# multiswitch2_2.net
KiCad netlist of a schematic drawn in EAGLE
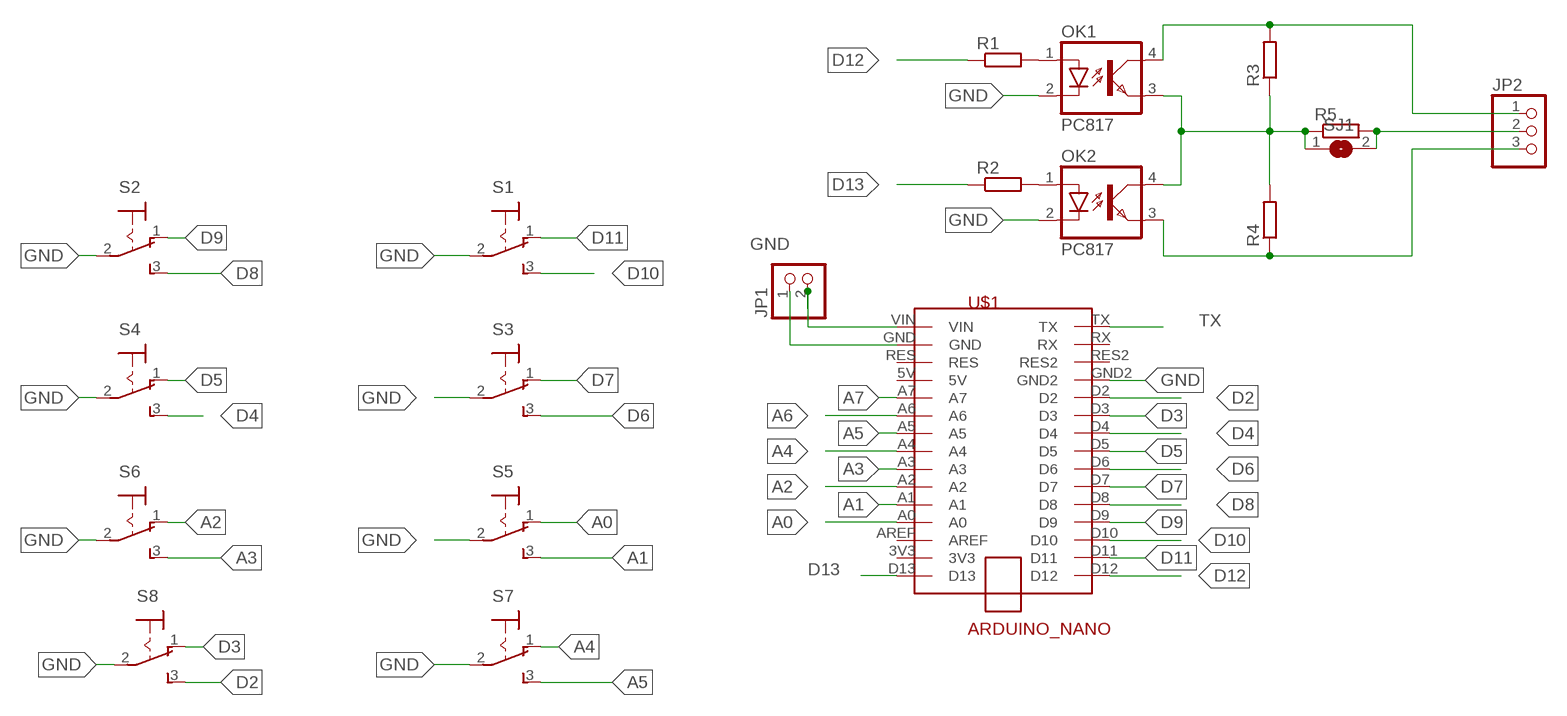
[diagram p0: schematic, sheet 1]

(export (version "E")
  (design (tool "Eeschema 10.0.6"))
  (components
    (comp (ref "JP1")
      (value "PINHD-1X2")
      (footprint "eagle-import:1X02")
      (libsource (lib "eagle-import") (part "PINHD-1X2"))
    )
    (comp (ref "JP2")
      (value "PINHD-1X3")
      (footprint "eagle-import:1X03")
      (libsource (lib "eagle-import") (part "PINHD-1X3"))
    )
    (comp (ref "OK1")
      (value "PC817")
      (footprint "eagle-import:DIL04")
      (fields (field (name "MPN") "PC817X4J000F"))
      (libsource (lib "eagle-import") (part "PC817"))
    )
    (comp (ref "OK2")
      (value "PC817")
      (footprint "eagle-import:DIL04")
      (fields (field (name "MPN") "PC817X4J000F"))
      (libsource (lib "eagle-import") (part "PC817"))
    )
    (comp (ref "R1")
      (value "R-EU_0204/7")
      (footprint "eagle-import:0204_7")
      (libsource (lib "eagle-import") (part "R-EU_0204/7"))
    )
    (comp (ref "R2")
      (value "R-EU_0204/7")
      (footprint "eagle-import:0204_7")
      (libsource (lib "eagle-import") (part "R-EU_0204/7"))
    )
    (comp (ref "R3")
      (value "R-EU_0204/7")
      (footprint "eagle-import:0204_7")
      (libsource (lib "eagle-import") (part "R-EU_0204/7"))
    )
    (comp (ref "R4")
      (value "R-EU_0204/7")
      (footprint "eagle-import:0204_7")
      (libsource (lib "eagle-import") (part "R-EU_0204/7"))
    )
    (comp (ref "R5")
      (value "R-EU_0204/7")
      (footprint "eagle-import:0204_7")
      (libsource (lib "eagle-import") (part "R-EU_0204/7"))
    )
    (comp (ref "S1")
      (value "M9040P")
      (footprint "eagle-import:M9040P")
      (libsource (lib "eagle-import") (part "M9040P"))
    )
    (comp (ref "S2")
      (value "M9040P")
      (footprint "eagle-import:M9040P")
      (libsource (lib "eagle-import") (part "M9040P"))
    )
    (comp (ref "S3")
      (value "M9040P")
      (footprint "eagle-import:M9040P")
      (libsource (lib "eagle-import") (part "M9040P"))
    )
    (comp (ref "S4")
      (value "M9040P")
      (footprint "eagle-import:M9040P")
      (libsource (lib "eagle-import") (part "M9040P"))
    )
    (comp (ref "S5")
      (value "M9040P")
      (footprint "eagle-import:M9040P")
      (libsource (lib "eagle-import") (part "M9040P"))
    )
    (comp (ref "S6")
      (value "M9040P")
      (footprint "eagle-import:M9040P")
      (libsource (lib "eagle-import") (part "M9040P"))
    )
    (comp (ref "S7")
      (value "M9040P")
      (footprint "eagle-import:M9040P")
      (libsource (lib "eagle-import") (part "M9040P"))
    )
    (comp (ref "S8")
      (value "M9040P")
      (footprint "eagle-import:M9040P")
      (libsource (lib "eagle-import") (part "M9040P"))
    )
    (comp (ref "SJ1") (value "SJ") (footprint "eagle-import:SJ") (libsource (lib "eagle-import") (part "SJ")))
    (comp (ref "U$1")
      (value "ARDUINO_NANO")
      (footprint "eagle-import:ARDUIN_NANO")
      (libsource (lib "eagle-import") (part "ARDUINO_NANO"))
    )
  )
  (nets
    (net (code "1") (name "/TX") (class "Default")
      (node (ref "U$1") (pin "TX") (pinfunction "TX_TX") (pintype "bidirectional"))
    )
    (net (code "2") (name "A0") (class "Default")
      (node (ref "S5") (pin "1") (pinfunction "O_1") (pintype "passive"))
      (node (ref "U$1") (pin "A0") (pinfunction "A0_A0") (pintype "bidirectional"))
    )
    (net (code "3") (name "A1") (class "Default")
      (node (ref "S5") (pin "3") (pinfunction "S_3") (pintype "passive"))
      (node (ref "U$1") (pin "A1") (pinfunction "A1_A1") (pintype "bidirectional"))
    )
    (net (code "4") (name "A2") (class "Default")
      (node (ref "S6") (pin "1") (pinfunction "O_1") (pintype "passive"))
      (node (ref "U$1") (pin "A2") (pinfunction "A2_A2") (pintype "bidirectional"))
    )
    (net (code "5") (name "A3") (class "Default")
      (node (ref "S6") (pin "3") (pinfunction "S_3") (pintype "passive"))
      (node (ref "U$1") (pin "A3") (pinfunction "A3_A3") (pintype "bidirectional"))
    )
    (net (code "6") (name "A4") (class "Default")
      (node (ref "S7") (pin "1") (pinfunction "O_1") (pintype "passive"))
      (node (ref "U$1") (pin "A4") (pinfunction "A4_A4") (pintype "bidirectional"))
    )
    (net (code "7") (name "A5") (class "Default")
      (node (ref "S7") (pin "3") (pinfunction "S_3") (pintype "passive"))
      (node (ref "U$1") (pin "A5") (pinfunction "A5_A5") (pintype "bidirectional"))
    )
    (net (code "8") (name "A6") (class "Default")
      (node (ref "U$1") (pin "A6") (pinfunction "A6_A6") (pintype "bidirectional"))
    )
    (net (code "9") (name "A7") (class "Default")
      (node (ref "U$1") (pin "A7") (pinfunction "A7_A7") (pintype "bidirectional"))
    )
    (net (code "10") (name "D2") (class "Default")
      (node (ref "S8") (pin "3") (pinfunction "S_3") (pintype "passive"))
      (node (ref "U$1") (pin "D2") (pinfunction "D2_D2") (pintype "bidirectional"))
    )
    (net (code "11") (name "D3") (class "Default")
      (node (ref "S8") (pin "1") (pinfunction "O_1") (pintype "passive"))
      (node (ref "U$1") (pin "D3") (pinfunction "D3_D3") (pintype "bidirectional"))
    )
    (net (code "12") (name "D4") (class "Default")
      (node (ref "S4") (pin "3") (pinfunction "S_3") (pintype "passive"))
      (node (ref "U$1") (pin "D4") (pinfunction "D4_D4") (pintype "bidirectional"))
    )
    (net (code "13") (name "D5") (class "Default")
      (node (ref "S4") (pin "1") (pinfunction "O_1") (pintype "passive"))
      (node (ref "U$1") (pin "D5") (pinfunction "D5_D5") (pintype "bidirectional"))
    )
    (net (code "14") (name "D6") (class "Default")
      (node (ref "S3") (pin "3") (pinfunction "S_3") (pintype "passive"))
      (node (ref "U$1") (pin "D6") (pinfunction "D6_D6") (pintype "bidirectional"))
    )
    (net (code "15") (name "D7") (class "Default")
      (node (ref "S3") (pin "1") (pinfunction "O_1") (pintype "passive"))
      (node (ref "U$1") (pin "D7") (pinfunction "D7_D7") (pintype "bidirectional"))
    )
    (net (code "16") (name "D8") (class "Default")
      (node (ref "S2") (pin "3") (pinfunction "S_3") (pintype "passive"))
      (node (ref "U$1") (pin "D8") (pinfunction "D8_D8") (pintype "bidirectional"))
    )
    (net (code "17") (name "D9") (class "Default")
      (node (ref "S2") (pin "1") (pinfunction "O_1") (pintype "passive"))
      (node (ref "U$1") (pin "D9") (pinfunction "D9_D9") (pintype "bidirectional"))
    )
    (net (code "18") (name "D10") (class "Default")
      (node (ref "S1") (pin "3") (pinfunction "S_3") (pintype "passive"))
      (node (ref "U$1") (pin "D10") (pinfunction "D10_D10") (pintype "bidirectional"))
    )
    (net (code "19") (name "D11") (class "Default")
      (node (ref "S1") (pin "1") (pinfunction "O_1") (pintype "passive"))
      (node (ref "U$1") (pin "D11") (pinfunction "D11_D11") (pintype "bidirectional"))
    )
    (net (code "20") (name "D12") (class "Default")
      (node (ref "R1") (pin "1") (pinfunction "1_1") (pintype "passive"))
      (node (ref "U$1") (pin "D12") (pinfunction "D12_D12") (pintype "bidirectional"))
    )
    (net (code "21") (name "D13") (class "Default")
      (node (ref "R2") (pin "1") (pinfunction "1_1") (pintype "passive"))
      (node (ref "U$1") (pin "D13") (pinfunction "D13_D13") (pintype "bidirectional"))
    )
    (net (code "22") (name "GND") (class "Default")
      (node (ref "JP1") (pin "1") (pinfunction "1_1") (pintype "passive"))
      (node (ref "OK1") (pin "2") (pinfunction "C_2") (pintype "passive"))
      (node (ref "OK2") (pin "2") (pinfunction "C_2") (pintype "passive"))
      (node (ref "S1") (pin "2") (pinfunction "P_2") (pintype "passive"))
      (node (ref "S2") (pin "2") (pinfunction "P_2") (pintype "passive"))
      (node (ref "S3") (pin "2") (pinfunction "P_2") (pintype "passive"))
      (node (ref "S4") (pin "2") (pinfunction "P_2") (pintype "passive"))
      (node (ref "S5") (pin "2") (pinfunction "P_2") (pintype "passive"))
      (node (ref "S6") (pin "2") (pinfunction "P_2") (pintype "passive"))
      (node (ref "S7") (pin "2") (pinfunction "P_2") (pintype "passive"))
      (node (ref "S8") (pin "2") (pinfunction "P_2") (pintype "passive"))
      (node (ref "U$1") (pin "GND") (pinfunction "GND_GND") (pintype "bidirectional"))
      (node (ref "U$1") (pin "GND2") (pinfunction "GND2_GND2") (pintype "bidirectional"))
    )
    (net (code "23") (name "Net-(JP1-Pad2)") (class "Default")
      (node (ref "JP1") (pin "2") (pinfunction "2_2") (pintype "passive"))
      (node (ref "U$1") (pin "VIN") (pinfunction "VIN_VIN") (pintype "bidirectional"))
    )
    (net (code "24") (name "Net-(JP2-Pad2)") (class "Default")
      (node (ref "JP2") (pin "2") (pinfunction "2_2") (pintype "passive"))
      (node (ref "R5") (pin "2") (pinfunction "2_2") (pintype "passive"))
      (node (ref "SJ1") (pin "2") (pinfunction "2_2") (pintype "passive"))
    )
    (net (code "25") (name "Net-(OK1-A)") (class "Default")
      (node (ref "OK1") (pin "1") (pinfunction "A_1") (pintype "passive"))
      (node (ref "R1") (pin "2") (pinfunction "2_2") (pintype "passive"))
    )
    (net (code "26") (name "Net-(OK1-COL)") (class "Default")
      (node (ref "JP2") (pin "1") (pinfunction "1_1") (pintype "passive"))
      (node (ref "OK1") (pin "4") (pinfunction "COL_4") (pintype "passive"))
      (node (ref "R3") (pin "2") (pinfunction "2_2") (pintype "passive"))
    )
    (net (code "27") (name "Net-(OK1-EMIT)") (class "Default")
      (node (ref "OK1") (pin "3") (pinfunction "EMIT_3") (pintype "passive"))
      (node (ref "OK2") (pin "4") (pinfunction "COL_4") (pintype "passive"))
      (node (ref "R3") (pin "1") (pinfunction "1_1") (pintype "passive"))
      (node (ref "R4") (pin "2") (pinfunction "2_2") (pintype "passive"))
      (node (ref "R5") (pin "1") (pinfunction "1_1") (pintype "passive"))
      (node (ref "SJ1") (pin "1") (pinfunction "1_1") (pintype "passive"))
    )
    (net (code "28") (name "Net-(OK2-A)") (class "Default")
      (node (ref "OK2") (pin "1") (pinfunction "A_1") (pintype "passive"))
      (node (ref "R2") (pin "2") (pinfunction "2_2") (pintype "passive"))
    )
    (net (code "29") (name "Net-(OK2-EMIT)") (class "Default")
      (node (ref "JP2") (pin "3") (pinfunction "3_3") (pintype "passive"))
      (node (ref "OK2") (pin "3") (pinfunction "EMIT_3") (pintype "passive"))
      (node (ref "R4") (pin "1") (pinfunction "1_1") (pintype "passive"))
    )
    (net (code "30") (name "unconnected-(U$1-Pad3V3)") (class "Default")
      (node (ref "U$1") (pin "3V3") (pinfunction "3V3_3V3") (pintype "bidirectional"))
    )
    (net (code "31") (name "unconnected-(U$1-Pad5V)") (class "Default")
      (node (ref "U$1") (pin "5V") (pinfunction "5V_5V") (pintype "bidirectional"))
    )
    (net (code "32") (name "unconnected-(U$1-PadAREF)") (class "Default")
      (node (ref "U$1") (pin "AREF") (pinfunction "AREF_AREF") (pintype "bidirectional"))
    )
    (net (code "33") (name "unconnected-(U$1-PadRES)") (class "Default")
      (node (ref "U$1") (pin "RES") (pinfunction "RES_RES") (pintype "bidirectional"))
    )
    (net (code "34") (name "unconnected-(U$1-PadRES2)") (class "Default")
      (node (ref "U$1") (pin "RES2") (pinfunction "RES2_RES2") (pintype "bidirectional"))
    )
    (net (code "35") (name "unconnected-(U$1-PadRX)") (class "Default")
      (node (ref "U$1") (pin "RX") (pinfunction "RX_RX") (pintype "bidirectional"))
    )
  )
)
